# LiPo_Charger_MCP73831.net
KiCad netlist of a schematic drawn in EAGLE
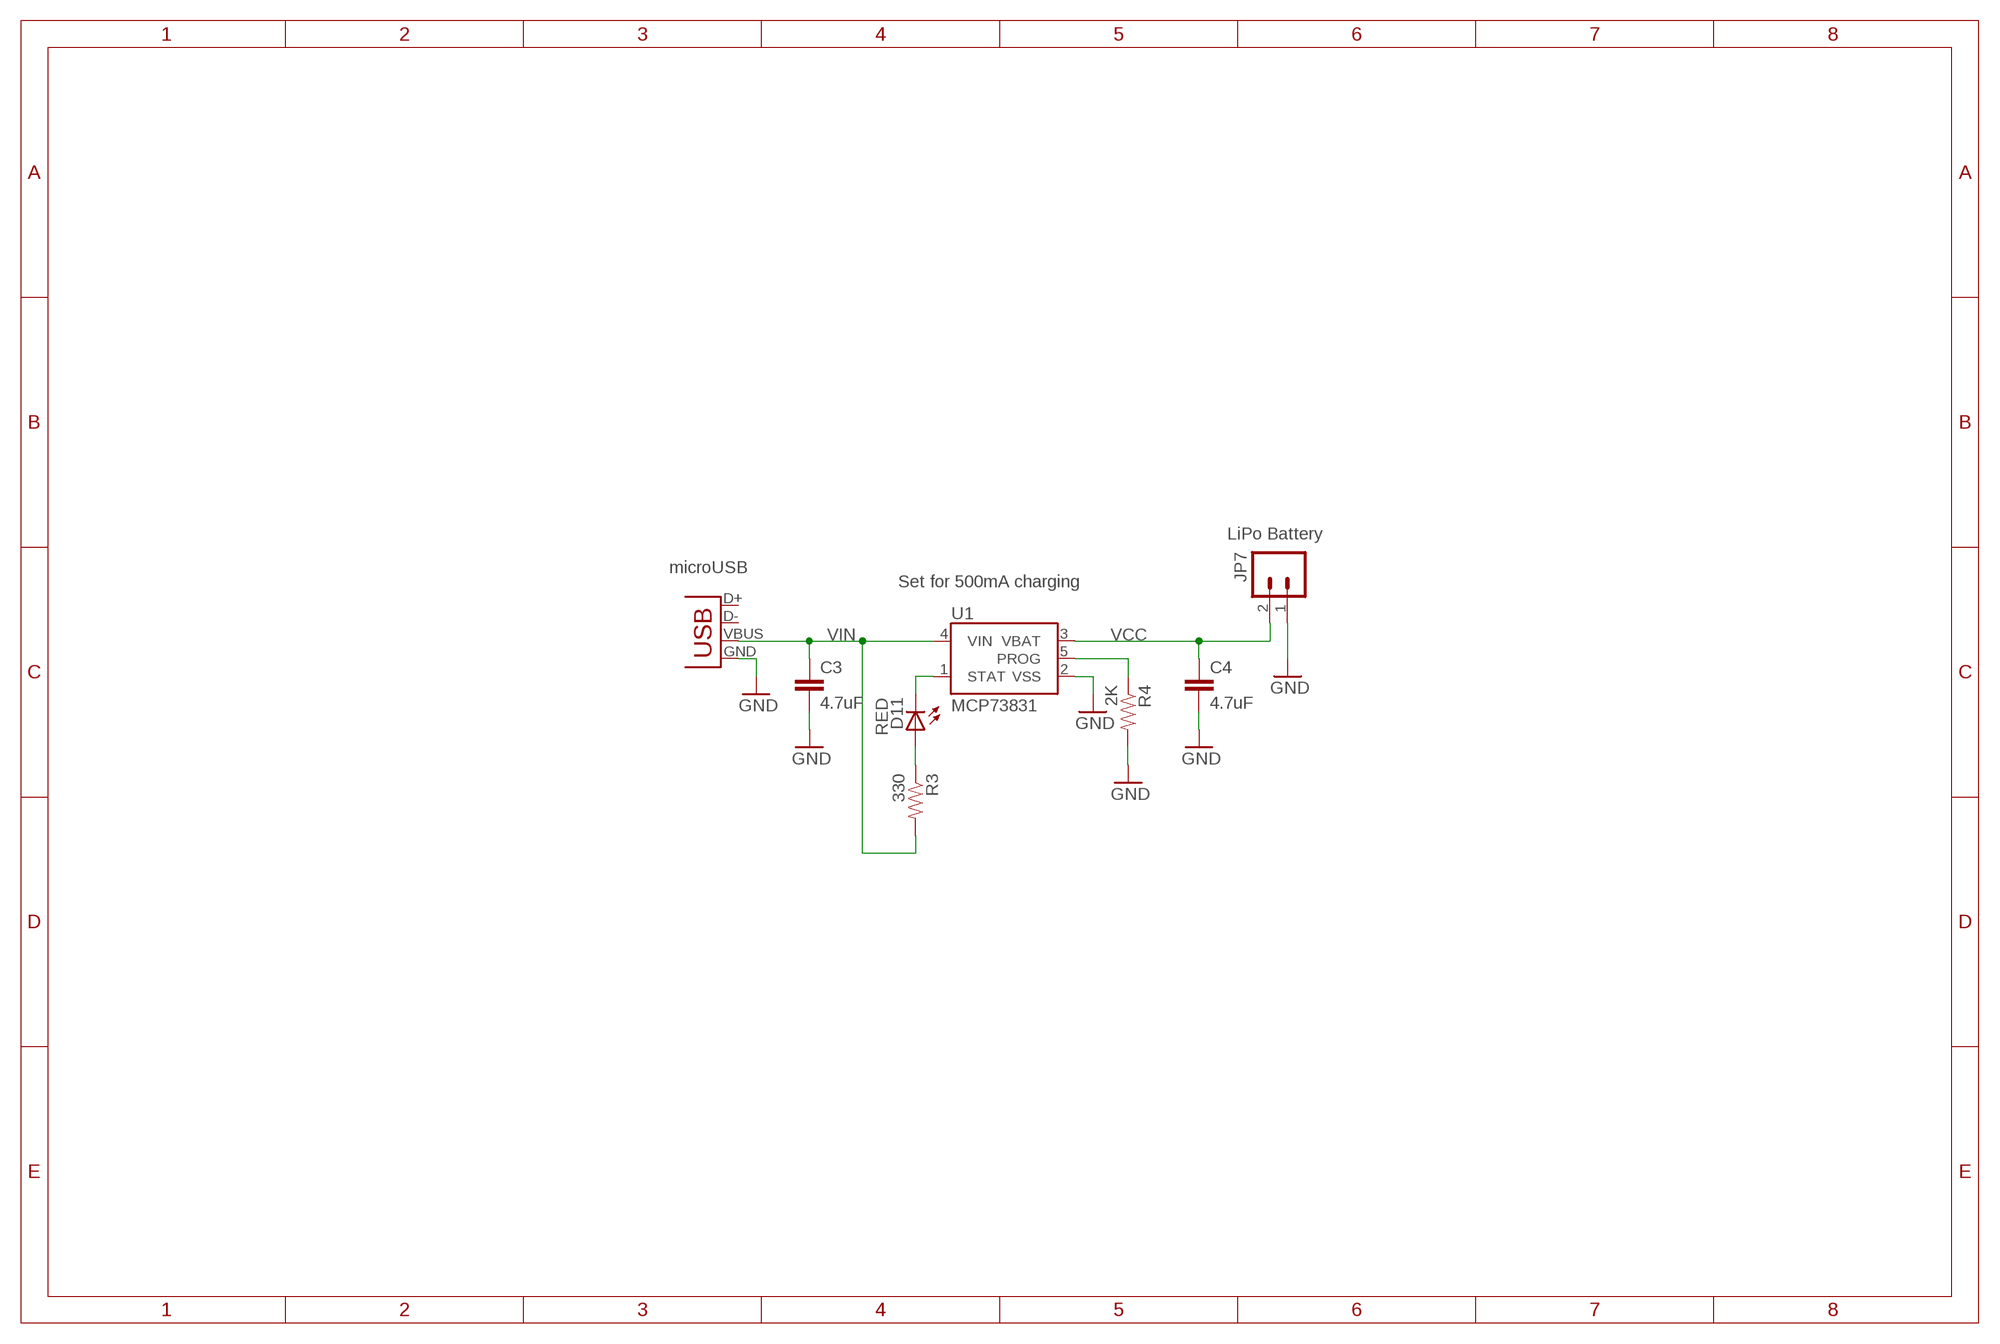
[diagram p0: schematic, sheet 1]

(export (version "E")
  (design (tool "Eeschema 10.0.6"))
  (components
    (comp (ref "C3")
      (value "4.7uF")
      (footprint "eagle-import:0402-CAP")
      (libsource (lib "eagle-import") (part "CAP0402-CAP"))
    )
    (comp (ref "C4")
      (value "4.7uF")
      (footprint "eagle-import:0402-CAP")
      (libsource (lib "eagle-import") (part "CAP0402-CAP"))
    )
    (comp (ref "D11")
      (value "RED")
      (footprint "eagle-import:LED-0603")
      (libsource (lib "eagle-import") (part "LED0603"))
    )
    (comp (ref "JP7")
      (value "LiPo Battery")
      (footprint "eagle-import:JST-2-SMD")
      (libsource (lib "eagle-import") (part "M02-JST-2MM-SMT"))
    )
    (comp (ref "R3")
      (value "330")
      (footprint "eagle-import:0402-RES")
      (libsource (lib "eagle-import") (part "RESISTOR0402-RES"))
    )
    (comp (ref "R4")
      (value "2K")
      (footprint "eagle-import:0402-RES")
      (libsource (lib "eagle-import") (part "RESISTOR0402-RES"))
    )
    (comp (ref "U1")
      (value "MCP73831")
      (footprint "eagle-import:SOT23-5")
      (libsource (lib "eagle-import") (part "MCP73831"))
    )
    (comp (ref "X1")
      (value "Micro USB")
      (footprint "eagle-import:USB-MICROB")
      (libsource (lib "eagle-import") (part "USB-MICROB"))
    )
  )
  (nets
    (net (code "1") (name "/VCC") (class "Default")
      (node (ref "C4") (pin "1") (pinfunction "1_1") (pintype "passive"))
      (node (ref "JP7") (pin "2") (pinfunction "2_2") (pintype "passive"))
      (node (ref "U1") (pin "3") (pinfunction "VBAT_3") (pintype "power_in"))
    )
    (net (code "2") (name "/VIN") (class "Default")
      (node (ref "C3") (pin "1") (pinfunction "1_1") (pintype "passive"))
      (node (ref "R3") (pin "2") (pinfunction "2_2") (pintype "passive"))
      (node (ref "U1") (pin "4") (pinfunction "VIN_4") (pintype "power_in"))
      (node (ref "X1") (pin "VBUS") (pinfunction "VBUS_VBUS") (pintype "bidirectional"))
    )
    (net (code "3") (name "GND") (class "Default")
      (node (ref "C3") (pin "2") (pinfunction "2_2") (pintype "passive"))
      (node (ref "C4") (pin "2") (pinfunction "2_2") (pintype "passive"))
      (node (ref "JP7") (pin "1") (pinfunction "1_1") (pintype "passive"))
      (node (ref "R4") (pin "2") (pinfunction "2_2") (pintype "passive"))
      (node (ref "U1") (pin "2") (pinfunction "VSS_2") (pintype "power_in"))
      (node (ref "X1") (pin "GND") (pinfunction "GND_GND") (pintype "bidirectional"))
    )
    (net (code "4") (name "Net-(D11-PadA)") (class "Default")
      (node (ref "D11") (pin "A") (pinfunction "A_A") (pintype "passive"))
      (node (ref "R3") (pin "1") (pinfunction "1_1") (pintype "passive"))
    )
    (net (code "5") (name "Net-(U1-PROG)") (class "Default")
      (node (ref "R4") (pin "1") (pinfunction "1_1") (pintype "passive"))
      (node (ref "U1") (pin "5") (pinfunction "PROG_5") (pintype "input"))
    )
    (net (code "6") (name "Net-(U1-STAT)") (class "Default")
      (node (ref "D11") (pin "C") (pinfunction "C_C") (pintype "passive"))
      (node (ref "U1") (pin "1") (pinfunction "STAT_1") (pintype "output"))
    )
    (net (code "7") (name "unconnected-(X1-PadD+)") (class "Default")
      (node (ref "X1") (pin "D+") (pinfunction "D+_D+") (pintype "bidirectional"))
    )
    (net (code "8") (name "unconnected-(X1-PadD-)") (class "Default")
      (node (ref "X1") (pin "D-") (pinfunction "D-_D-") (pintype "bidirectional"))
    )
  )
)
